# clock-temp-touch.net
KiCad netlist of a schematic drawn in Altium Designer
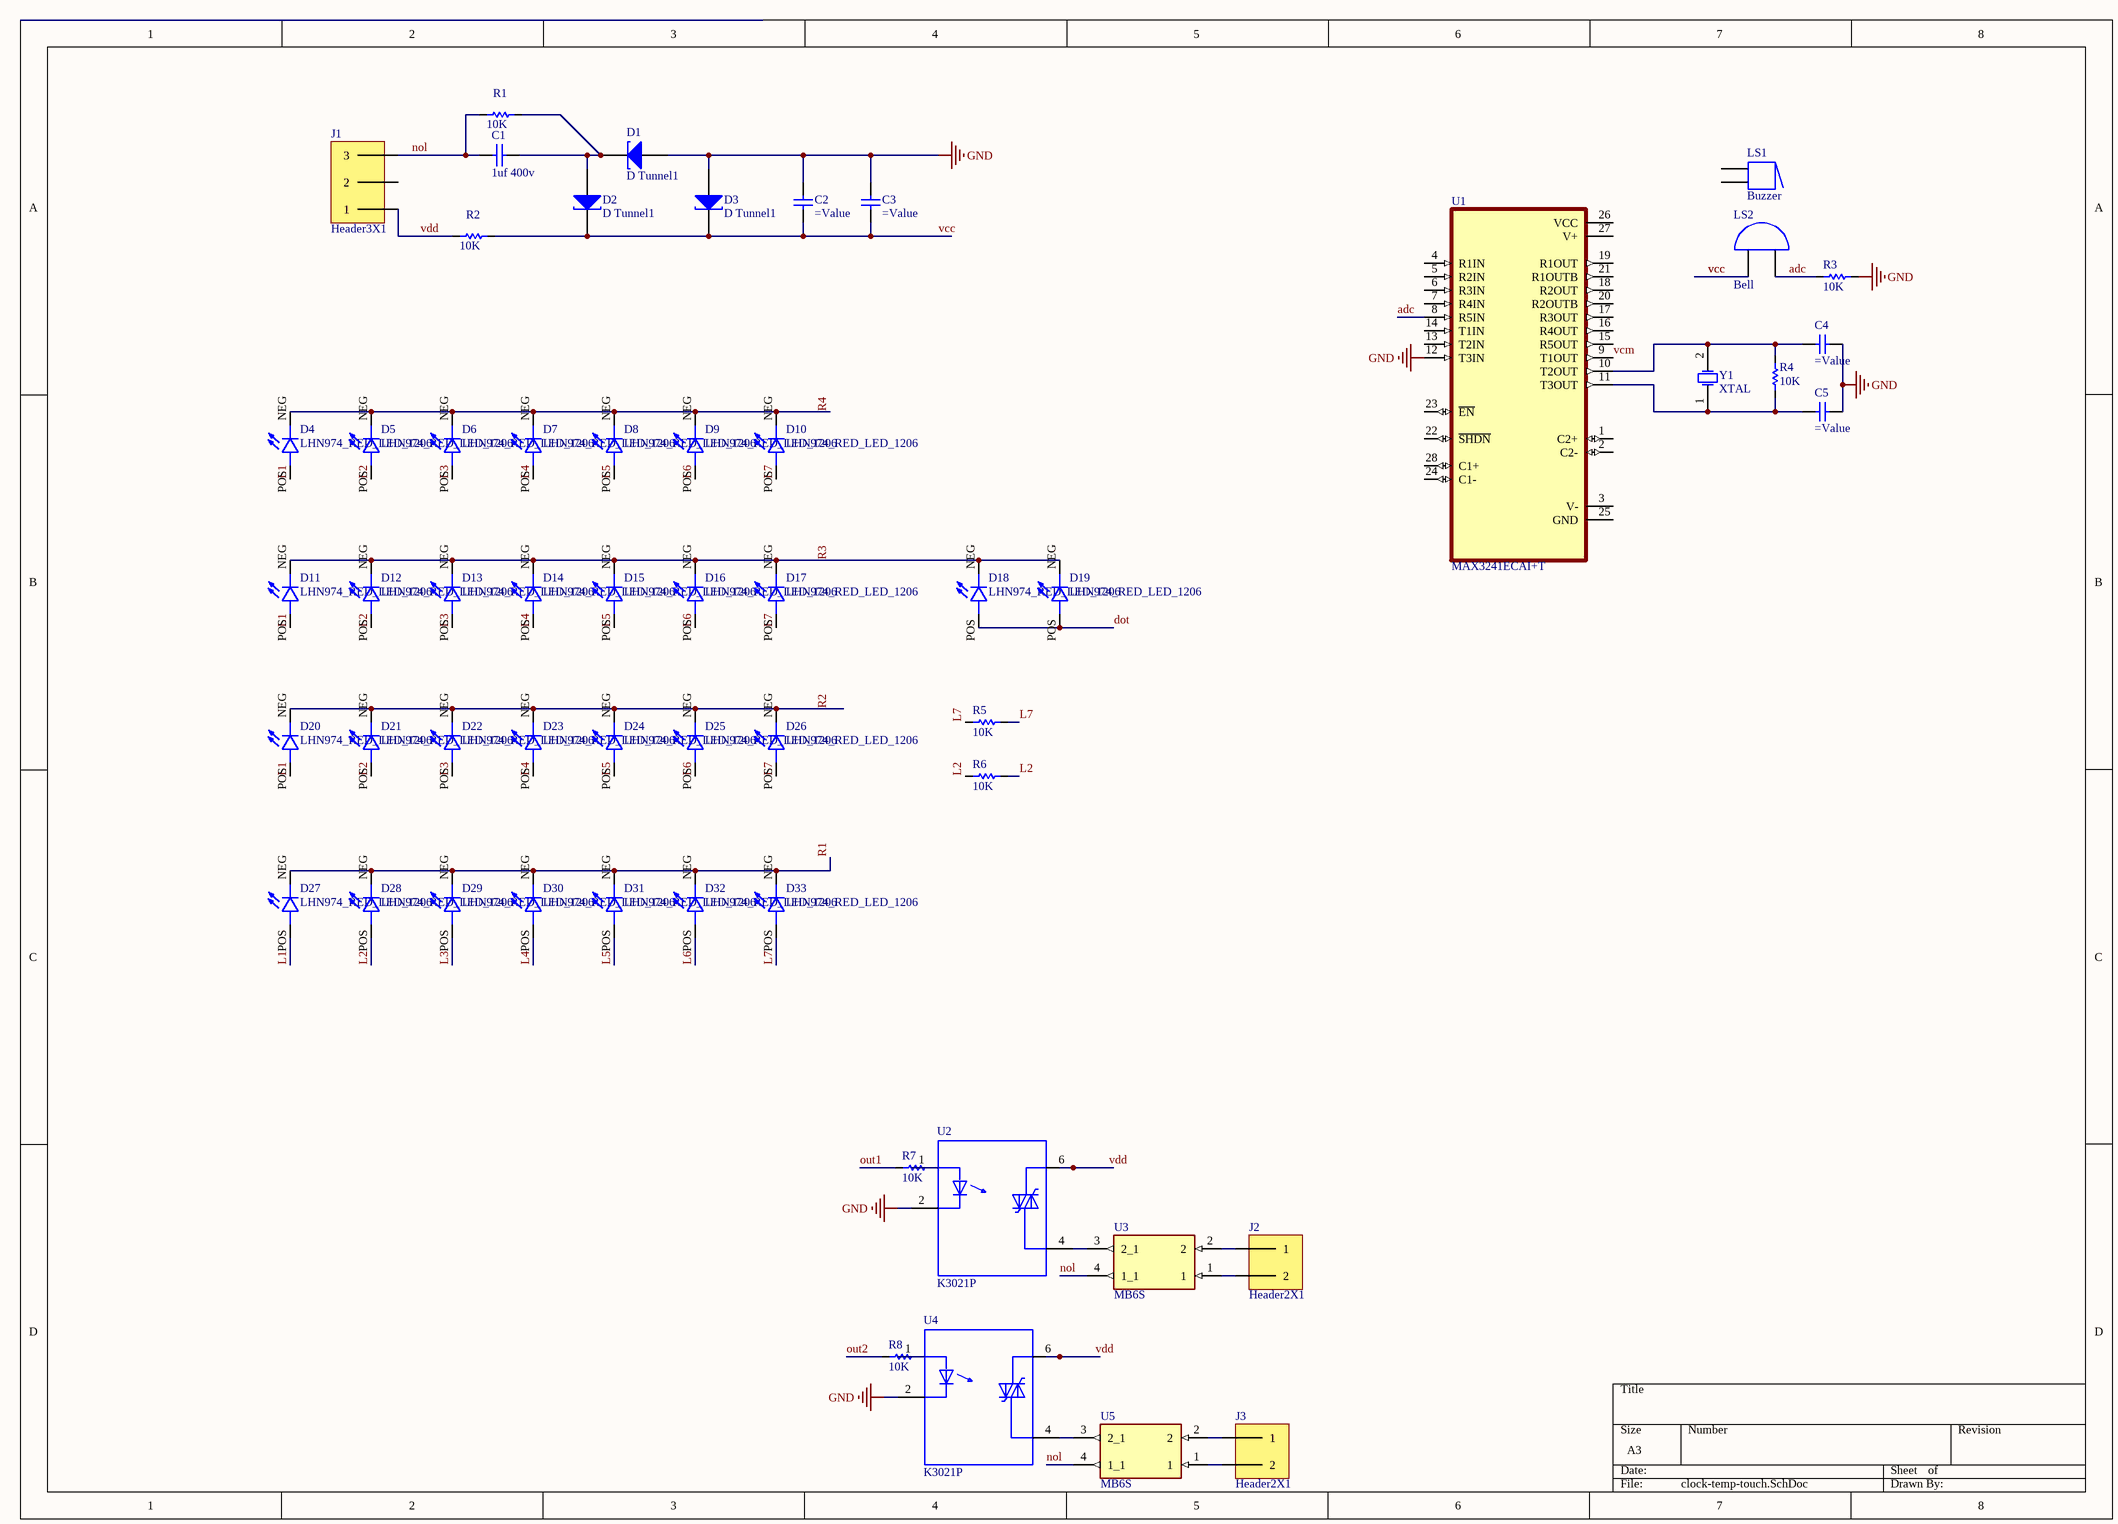
[diagram p0: clock-temp-touch.SchDoc]

(export (version "E")
  (design (tool "Eeschema 10.0.6"))
  (components
    (comp (ref "C1")
      (value "1uf 400v")
      (footprint "1uf 400v")
      (description "Capacitor 24*9mm")
      (fields (field (name "DESIGNER") "Seyed Mohsen Ghasemain"))
      (libsource (lib "PicPars.com_usefully_Library") (part "1uf 400v"))
    )
    (comp (ref "C2")
      (value "~")
      (footprint "CAP 1206")
      (description "Capacitor")
      (libsource (lib "AltiumLib1") (part "Capacitor"))
    )
    (comp (ref "C3")
      (value "~")
      (footprint "CAP 1206")
      (description "Capacitor")
      (libsource (lib "AltiumLib1") (part "Capacitor"))
    )
    (comp (ref "C4")
      (value "~")
      (footprint "CAP 1206")
      (description "Capacitor")
      (libsource (lib "AltiumLib1") (part "Capacitor"))
    )
    (comp (ref "C5")
      (value "~")
      (footprint "CAP 1206")
      (description "Capacitor")
      (libsource (lib "AltiumLib1") (part "Capacitor"))
    )
    (comp (ref "D1")
      (value "D Tunnel1")
      (footprint "3.2X1.6X1.1")
      (description "Tunnel Diode - RLC Model")
      (fields (field (name "PUBLISHER") "Altium Limited"))
      (libsource (lib "Miscellaneous Devices") (part "D Tunnel1"))
    )
    (comp (ref "D2")
      (value "D Tunnel1")
      (footprint "3.2X1.6X1.1")
      (description "Tunnel Diode - RLC Model")
      (fields (field (name "PUBLISHER") "Altium Limited"))
      (libsource (lib "Miscellaneous Devices") (part "D Tunnel1"))
    )
    (comp (ref "D3")
      (value "D Tunnel1")
      (footprint "3.2X1.6X1.1")
      (description "Tunnel Diode - RLC Model")
      (fields (field (name "PUBLISHER") "Altium Limited"))
      (libsource (lib "Miscellaneous Devices") (part "D Tunnel1"))
    )
    (comp (ref "D4")
      (value "LHN974_RED_LED_1206")
      (footprint "LEDC3216X120N")
      (description "2.6 V Red LED SMD")
      (fields (field (name "MP") "LHN974 RED LED 1206") (field (name "MF") "Osram"))
      (libsource (lib "LHN974_RED_LED_1206") (part "LHN974_RED_LED_1206"))
    )
    (comp (ref "D5")
      (value "LHN974_RED_LED_1206")
      (footprint "LEDC3216X120N")
      (description "2.6 V Red LED SMD")
      (fields (field (name "MP") "LHN974 RED LED 1206") (field (name "MF") "Osram"))
      (libsource (lib "LHN974_RED_LED_1206") (part "LHN974_RED_LED_1206"))
    )
    (comp (ref "D6")
      (value "LHN974_RED_LED_1206")
      (footprint "LEDC3216X120N")
      (description "2.6 V Red LED SMD")
      (fields (field (name "MP") "LHN974 RED LED 1206") (field (name "MF") "Osram"))
      (libsource (lib "LHN974_RED_LED_1206") (part "LHN974_RED_LED_1206"))
    )
    (comp (ref "D7")
      (value "LHN974_RED_LED_1206")
      (footprint "LEDC3216X120N")
      (description "2.6 V Red LED SMD")
      (fields (field (name "MP") "LHN974 RED LED 1206") (field (name "MF") "Osram"))
      (libsource (lib "LHN974_RED_LED_1206") (part "LHN974_RED_LED_1206"))
    )
    (comp (ref "D8")
      (value "LHN974_RED_LED_1206")
      (footprint "LEDC3216X120N")
      (description "2.6 V Red LED SMD")
      (fields (field (name "MP") "LHN974 RED LED 1206") (field (name "MF") "Osram"))
      (libsource (lib "LHN974_RED_LED_1206") (part "LHN974_RED_LED_1206"))
    )
    (comp (ref "D9")
      (value "LHN974_RED_LED_1206")
      (footprint "LEDC3216X120N")
      (description "2.6 V Red LED SMD")
      (fields (field (name "MP") "LHN974 RED LED 1206") (field (name "MF") "Osram"))
      (libsource (lib "LHN974_RED_LED_1206") (part "LHN974_RED_LED_1206"))
    )
    (comp (ref "D10")
      (value "LHN974_RED_LED_1206")
      (footprint "LEDC3216X120N")
      (description "2.6 V Red LED SMD")
      (fields (field (name "MP") "LHN974 RED LED 1206") (field (name "MF") "Osram"))
      (libsource (lib "LHN974_RED_LED_1206") (part "LHN974_RED_LED_1206"))
    )
    (comp (ref "D11")
      (value "LHN974_RED_LED_1206")
      (footprint "LEDC3216X120N")
      (description "2.6 V Red LED SMD")
      (fields (field (name "MP") "LHN974 RED LED 1206") (field (name "MF") "Osram"))
      (libsource (lib "LHN974_RED_LED_1206") (part "LHN974_RED_LED_1206"))
    )
    (comp (ref "D12")
      (value "LHN974_RED_LED_1206")
      (footprint "LEDC3216X120N")
      (description "2.6 V Red LED SMD")
      (fields (field (name "MP") "LHN974 RED LED 1206") (field (name "MF") "Osram"))
      (libsource (lib "LHN974_RED_LED_1206") (part "LHN974_RED_LED_1206"))
    )
    (comp (ref "D13")
      (value "LHN974_RED_LED_1206")
      (footprint "LEDC3216X120N")
      (description "2.6 V Red LED SMD")
      (fields (field (name "MP") "LHN974 RED LED 1206") (field (name "MF") "Osram"))
      (libsource (lib "LHN974_RED_LED_1206") (part "LHN974_RED_LED_1206"))
    )
    (comp (ref "D14")
      (value "LHN974_RED_LED_1206")
      (footprint "LEDC3216X120N")
      (description "2.6 V Red LED SMD")
      (fields (field (name "MP") "LHN974 RED LED 1206") (field (name "MF") "Osram"))
      (libsource (lib "LHN974_RED_LED_1206") (part "LHN974_RED_LED_1206"))
    )
    (comp (ref "D15")
      (value "LHN974_RED_LED_1206")
      (footprint "LEDC3216X120N")
      (description "2.6 V Red LED SMD")
      (fields (field (name "MP") "LHN974 RED LED 1206") (field (name "MF") "Osram"))
      (libsource (lib "LHN974_RED_LED_1206") (part "LHN974_RED_LED_1206"))
    )
    (comp (ref "D16")
      (value "LHN974_RED_LED_1206")
      (footprint "LEDC3216X120N")
      (description "2.6 V Red LED SMD")
      (fields (field (name "MP") "LHN974 RED LED 1206") (field (name "MF") "Osram"))
      (libsource (lib "LHN974_RED_LED_1206") (part "LHN974_RED_LED_1206"))
    )
    (comp (ref "D17")
      (value "LHN974_RED_LED_1206")
      (footprint "LEDC3216X120N")
      (description "2.6 V Red LED SMD")
      (fields (field (name "MP") "LHN974 RED LED 1206") (field (name "MF") "Osram"))
      (libsource (lib "LHN974_RED_LED_1206") (part "LHN974_RED_LED_1206"))
    )
    (comp (ref "D18")
      (value "LHN974_RED_LED_1206")
      (footprint "LEDC3216X120N")
      (description "2.6 V Red LED SMD")
      (fields (field (name "MP") "LHN974 RED LED 1206") (field (name "MF") "Osram"))
      (libsource (lib "LHN974_RED_LED_1206") (part "LHN974_RED_LED_1206"))
    )
    (comp (ref "D19")
      (value "LHN974_RED_LED_1206")
      (footprint "LEDC3216X120N")
      (description "2.6 V Red LED SMD")
      (fields (field (name "MP") "LHN974 RED LED 1206") (field (name "MF") "Osram"))
      (libsource (lib "LHN974_RED_LED_1206") (part "LHN974_RED_LED_1206"))
    )
    (comp (ref "D20")
      (value "LHN974_RED_LED_1206")
      (footprint "LEDC3216X120N")
      (description "2.6 V Red LED SMD")
      (fields (field (name "MP") "LHN974 RED LED 1206") (field (name "MF") "Osram"))
      (libsource (lib "LHN974_RED_LED_1206") (part "LHN974_RED_LED_1206"))
    )
    (comp (ref "D21")
      (value "LHN974_RED_LED_1206")
      (footprint "LEDC3216X120N")
      (description "2.6 V Red LED SMD")
      (fields (field (name "MP") "LHN974 RED LED 1206") (field (name "MF") "Osram"))
      (libsource (lib "LHN974_RED_LED_1206") (part "LHN974_RED_LED_1206"))
    )
    (comp (ref "D22")
      (value "LHN974_RED_LED_1206")
      (footprint "LEDC3216X120N")
      (description "2.6 V Red LED SMD")
      (fields (field (name "MP") "LHN974 RED LED 1206") (field (name "MF") "Osram"))
      (libsource (lib "LHN974_RED_LED_1206") (part "LHN974_RED_LED_1206"))
    )
    (comp (ref "D23")
      (value "LHN974_RED_LED_1206")
      (footprint "LEDC3216X120N")
      (description "2.6 V Red LED SMD")
      (fields (field (name "MP") "LHN974 RED LED 1206") (field (name "MF") "Osram"))
      (libsource (lib "LHN974_RED_LED_1206") (part "LHN974_RED_LED_1206"))
    )
    (comp (ref "D24")
      (value "LHN974_RED_LED_1206")
      (footprint "LEDC3216X120N")
      (description "2.6 V Red LED SMD")
      (fields (field (name "MP") "LHN974 RED LED 1206") (field (name "MF") "Osram"))
      (libsource (lib "LHN974_RED_LED_1206") (part "LHN974_RED_LED_1206"))
    )
    (comp (ref "D25")
      (value "LHN974_RED_LED_1206")
      (footprint "LEDC3216X120N")
      (description "2.6 V Red LED SMD")
      (fields (field (name "MP") "LHN974 RED LED 1206") (field (name "MF") "Osram"))
      (libsource (lib "LHN974_RED_LED_1206") (part "LHN974_RED_LED_1206"))
    )
    (comp (ref "D26")
      (value "LHN974_RED_LED_1206")
      (footprint "LEDC3216X120N")
      (description "2.6 V Red LED SMD")
      (fields (field (name "MP") "LHN974 RED LED 1206") (field (name "MF") "Osram"))
      (libsource (lib "LHN974_RED_LED_1206") (part "LHN974_RED_LED_1206"))
    )
    (comp (ref "D27")
      (value "LHN974_RED_LED_1206")
      (footprint "LEDC3216X120N")
      (description "2.6 V Red LED SMD")
      (fields (field (name "MP") "LHN974 RED LED 1206") (field (name "MF") "Osram"))
      (libsource (lib "LHN974_RED_LED_1206") (part "LHN974_RED_LED_1206"))
    )
    (comp (ref "D28")
      (value "LHN974_RED_LED_1206")
      (footprint "LEDC3216X120N")
      (description "2.6 V Red LED SMD")
      (fields (field (name "MP") "LHN974 RED LED 1206") (field (name "MF") "Osram"))
      (libsource (lib "LHN974_RED_LED_1206") (part "LHN974_RED_LED_1206"))
    )
    (comp (ref "D29")
      (value "LHN974_RED_LED_1206")
      (footprint "LEDC3216X120N")
      (description "2.6 V Red LED SMD")
      (fields (field (name "MP") "LHN974 RED LED 1206") (field (name "MF") "Osram"))
      (libsource (lib "LHN974_RED_LED_1206") (part "LHN974_RED_LED_1206"))
    )
    (comp (ref "D30")
      (value "LHN974_RED_LED_1206")
      (footprint "LEDC3216X120N")
      (description "2.6 V Red LED SMD")
      (fields (field (name "MP") "LHN974 RED LED 1206") (field (name "MF") "Osram"))
      (libsource (lib "LHN974_RED_LED_1206") (part "LHN974_RED_LED_1206"))
    )
    (comp (ref "D31")
      (value "LHN974_RED_LED_1206")
      (footprint "LEDC3216X120N")
      (description "2.6 V Red LED SMD")
      (fields (field (name "MP") "LHN974 RED LED 1206") (field (name "MF") "Osram"))
      (libsource (lib "LHN974_RED_LED_1206") (part "LHN974_RED_LED_1206"))
    )
    (comp (ref "D32")
      (value "LHN974_RED_LED_1206")
      (footprint "LEDC3216X120N")
      (description "2.6 V Red LED SMD")
      (fields (field (name "MP") "LHN974 RED LED 1206") (field (name "MF") "Osram"))
      (libsource (lib "LHN974_RED_LED_1206") (part "LHN974_RED_LED_1206"))
    )
    (comp (ref "D33")
      (value "LHN974_RED_LED_1206")
      (footprint "LEDC3216X120N")
      (description "2.6 V Red LED SMD")
      (fields (field (name "MP") "LHN974 RED LED 1206") (field (name "MF") "Osram"))
      (libsource (lib "LHN974_RED_LED_1206") (part "LHN974_RED_LED_1206"))
    )
    (comp (ref "J1")
      (value "Header3X1")
      (footprint "HEADER 3X1")
      (libsource (lib "AltiumLib1") (part "Header3X1"))
    )
    (comp (ref "J2")
      (value "Header2X1")
      (footprint "Header 2X1")
      (libsource (lib "AltiumLib1") (part "Header2X1"))
    )
    (comp (ref "J3")
      (value "Header2X1")
      (footprint "Header 2X1")
      (libsource (lib "AltiumLib1") (part "Header2X1"))
    )
    (comp (ref "LS1")
      (value "Buzzer")
      (footprint "ABSM-1574")
      (description "Magnetic Transducer Buzzer")
      (fields (field (name "PUBLISHER") "Altium Limited"))
      (libsource (lib "Miscellaneous Devices") (part "Buzzer"))
    )
    (comp (ref "LS2")
      (value "Bell")
      (footprint "PIN2")
      (description "Electrical Bell")
      (fields (field (name "PUBLISHER") "Altium Limited"))
      (libsource (lib "Miscellaneous Devices") (part "Bell"))
    )
    (comp (ref "R1")
      (value "10K")
      (footprint "RES 1206 (3216X08L)")
      (description "Resistor")
      (fields (field (name "TOLERANCE") "5%") (field (name "POWER") "1/4 W"))
      (libsource (lib "AltiumLib1") (part "Resistor"))
    )
    (comp (ref "R2")
      (value "10K")
      (footprint "Res-(2/1)")
      (description "Resistor")
      (fields (field (name "TOLERANCE") "5%") (field (name "POWER") "1/4 W"))
      (libsource (lib "AltiumLib1") (part "Resistor"))
    )
    (comp (ref "R3")
      (value "10K")
      (footprint "RES 1206 (3216X08L)")
      (description "Resistor")
      (fields (field (name "TOLERANCE") "5%") (field (name "POWER") "1/4 W"))
      (libsource (lib "AltiumLib1") (part "Resistor"))
    )
    (comp (ref "R4")
      (value "10K")
      (footprint "RES 1206 (3216X08L)")
      (description "Resistor")
      (fields (field (name "TOLERANCE") "5%") (field (name "POWER") "1/4 W"))
      (libsource (lib "AltiumLib1") (part "Resistor"))
    )
    (comp (ref "R5")
      (value "10K")
      (footprint "RES 1206 (3216X08L)")
      (description "Resistor")
      (fields (field (name "TOLERANCE") "5%") (field (name "POWER") "1/4 W"))
      (libsource (lib "AltiumLib1") (part "Resistor"))
    )
    (comp (ref "R6")
      (value "10K")
      (footprint "RES 1206 (3216X08L)")
      (description "Resistor")
      (fields (field (name "TOLERANCE") "5%") (field (name "POWER") "1/4 W"))
      (libsource (lib "AltiumLib1") (part "Resistor"))
    )
    (comp (ref "R7")
      (value "10K")
      (footprint "RES 1206 (3216X08L)")
      (description "Resistor")
      (fields (field (name "TOLERANCE") "5%") (field (name "POWER") "1/4 W"))
      (libsource (lib "AltiumLib1") (part "Resistor"))
    )
    (comp (ref "R8")
      (value "10K")
      (footprint "RES 1206 (3216X08L)")
      (description "Resistor")
      (fields (field (name "TOLERANCE") "5%") (field (name "POWER") "1/4 W"))
      (libsource (lib "AltiumLib1") (part "Resistor"))
    )
    (comp (ref "U1")
      (value "MAX3241ECAI+T")
      (footprint "SOP65P777X199-28N")
      (description "±15kV ESD-Protected, Down to 10nA, 3.0V to 5.5V, Up to 1Mbps, True RS-232 Transceivers")
      (fields (field (name "MF") "Analog Devices"))
      (libsource (lib "ssop28") (part "MAX3241ECAI+T"))
    )
    (comp (ref "U2")
      (value "K3021P")
      (footprint "DIP762W50P254L730H410Q6")
      (description "Optoisolator Triac Output 5300Vrms 1 Channel 6-DIP")
      (fields (field (name "MF") "Vishay Semiconductor"))
      (libsource (lib "K3021P") (part "K3021P"))
    )
    (comp (ref "U3")
      (value "MB6S")
      (footprint "SOIC245P670X270-4N")
      (description "Bridge Rectifier Single Phase Standard 600V Surface Mount 4-SOIC")
      (fields (field (name "MF") "ON Semiconductor") (field (name "DIGI-KEY_PART_NUMBER") "MB6SCT-ND"))
      (libsource (lib "MB6S") (part "MB6S"))
    )
    (comp (ref "U4")
      (value "K3021P")
      (footprint "DIP762W50P254L730H410Q6")
      (description "Optoisolator Triac Output 5300Vrms 1 Channel 6-DIP")
      (fields (field (name "MF") "Vishay Semiconductor"))
      (libsource (lib "K3021P") (part "K3021P"))
    )
    (comp (ref "U5")
      (value "MB6S")
      (footprint "SOIC245P670X270-4N")
      (description "Bridge Rectifier Single Phase Standard 600V Surface Mount 4-SOIC")
      (fields (field (name "MF") "ON Semiconductor") (field (name "DIGI-KEY_PART_NUMBER") "MB6SCT-ND"))
      (libsource (lib "MB6S") (part "MB6S"))
    )
    (comp (ref "Y1")
      (value "XTAL")
      (footprint "R38")
      (description "Crystal Oscillator")
      (fields (field (name "PUBLISHER") "Altium Limited"))
      (libsource (lib "Miscellaneous Devices") (part "XTAL"))
    )
  )
  (nets
    (net (code "1") (name "/L1") (class "Default")
      (node (ref "D11") (pin "POS") (pinfunction "POS_POS") (pintype "passive"))
      (node (ref "D20") (pin "POS") (pinfunction "POS_POS") (pintype "passive"))
      (node (ref "D27") (pin "POS") (pinfunction "POS_POS") (pintype "passive"))
      (node (ref "D4") (pin "POS") (pinfunction "POS_POS") (pintype "passive"))
    )
    (net (code "2") (name "/L2") (class "Default")
      (node (ref "D12") (pin "POS") (pinfunction "POS_POS") (pintype "passive"))
      (node (ref "D21") (pin "POS") (pinfunction "POS_POS") (pintype "passive"))
      (node (ref "D28") (pin "POS") (pinfunction "POS_POS") (pintype "passive"))
      (node (ref "D5") (pin "POS") (pinfunction "POS_POS") (pintype "passive"))
      (node (ref "R6") (pin "1") (pinfunction "1_1") (pintype "passive"))
      (node (ref "R6") (pin "2") (pinfunction "2_2") (pintype "passive"))
    )
    (net (code "3") (name "/L3") (class "Default")
      (node (ref "D13") (pin "POS") (pinfunction "POS_POS") (pintype "passive"))
      (node (ref "D22") (pin "POS") (pinfunction "POS_POS") (pintype "passive"))
      (node (ref "D29") (pin "POS") (pinfunction "POS_POS") (pintype "passive"))
      (node (ref "D6") (pin "POS") (pinfunction "POS_POS") (pintype "passive"))
    )
    (net (code "4") (name "/L4") (class "Default")
      (node (ref "D14") (pin "POS") (pinfunction "POS_POS") (pintype "passive"))
      (node (ref "D23") (pin "POS") (pinfunction "POS_POS") (pintype "passive"))
      (node (ref "D30") (pin "POS") (pinfunction "POS_POS") (pintype "passive"))
      (node (ref "D7") (pin "POS") (pinfunction "POS_POS") (pintype "passive"))
    )
    (net (code "5") (name "/L5") (class "Default")
      (node (ref "D15") (pin "POS") (pinfunction "POS_POS") (pintype "passive"))
      (node (ref "D24") (pin "POS") (pinfunction "POS_POS") (pintype "passive"))
      (node (ref "D31") (pin "POS") (pinfunction "POS_POS") (pintype "passive"))
      (node (ref "D8") (pin "POS") (pinfunction "POS_POS") (pintype "passive"))
    )
    (net (code "6") (name "/L6") (class "Default")
      (node (ref "D16") (pin "POS") (pinfunction "POS_POS") (pintype "passive"))
      (node (ref "D25") (pin "POS") (pinfunction "POS_POS") (pintype "passive"))
      (node (ref "D32") (pin "POS") (pinfunction "POS_POS") (pintype "passive"))
      (node (ref "D9") (pin "POS") (pinfunction "POS_POS") (pintype "passive"))
    )
    (net (code "7") (name "/L7") (class "Default")
      (node (ref "D10") (pin "POS") (pinfunction "POS_POS") (pintype "passive"))
      (node (ref "D17") (pin "POS") (pinfunction "POS_POS") (pintype "passive"))
      (node (ref "D26") (pin "POS") (pinfunction "POS_POS") (pintype "passive"))
      (node (ref "D33") (pin "POS") (pinfunction "POS_POS") (pintype "passive"))
      (node (ref "R5") (pin "1") (pinfunction "1_1") (pintype "passive"))
      (node (ref "R5") (pin "2") (pinfunction "2_2") (pintype "passive"))
    )
    (net (code "8") (name "/R1") (class "Default")
      (node (ref "D27") (pin "NEG") (pinfunction "NEG_NEG") (pintype "passive"))
      (node (ref "D28") (pin "NEG") (pinfunction "NEG_NEG") (pintype "passive"))
      (node (ref "D29") (pin "NEG") (pinfunction "NEG_NEG") (pintype "passive"))
      (node (ref "D30") (pin "NEG") (pinfunction "NEG_NEG") (pintype "passive"))
      (node (ref "D31") (pin "NEG") (pinfunction "NEG_NEG") (pintype "passive"))
      (node (ref "D32") (pin "NEG") (pinfunction "NEG_NEG") (pintype "passive"))
      (node (ref "D33") (pin "NEG") (pinfunction "NEG_NEG") (pintype "passive"))
    )
    (net (code "9") (name "/R2") (class "Default")
      (node (ref "D20") (pin "NEG") (pinfunction "NEG_NEG") (pintype "passive"))
      (node (ref "D21") (pin "NEG") (pinfunction "NEG_NEG") (pintype "passive"))
      (node (ref "D22") (pin "NEG") (pinfunction "NEG_NEG") (pintype "passive"))
      (node (ref "D23") (pin "NEG") (pinfunction "NEG_NEG") (pintype "passive"))
      (node (ref "D24") (pin "NEG") (pinfunction "NEG_NEG") (pintype "passive"))
      (node (ref "D25") (pin "NEG") (pinfunction "NEG_NEG") (pintype "passive"))
      (node (ref "D26") (pin "NEG") (pinfunction "NEG_NEG") (pintype "passive"))
    )
    (net (code "10") (name "/R3") (class "Default")
      (node (ref "D11") (pin "NEG") (pinfunction "NEG_NEG") (pintype "passive"))
      (node (ref "D12") (pin "NEG") (pinfunction "NEG_NEG") (pintype "passive"))
      (node (ref "D13") (pin "NEG") (pinfunction "NEG_NEG") (pintype "passive"))
      (node (ref "D14") (pin "NEG") (pinfunction "NEG_NEG") (pintype "passive"))
      (node (ref "D15") (pin "NEG") (pinfunction "NEG_NEG") (pintype "passive"))
      (node (ref "D16") (pin "NEG") (pinfunction "NEG_NEG") (pintype "passive"))
      (node (ref "D17") (pin "NEG") (pinfunction "NEG_NEG") (pintype "passive"))
      (node (ref "D18") (pin "NEG") (pinfunction "NEG_NEG") (pintype "passive"))
      (node (ref "D19") (pin "NEG") (pinfunction "NEG_NEG") (pintype "passive"))
    )
    (net (code "11") (name "/R4") (class "Default")
      (node (ref "D10") (pin "NEG") (pinfunction "NEG_NEG") (pintype "passive"))
      (node (ref "D4") (pin "NEG") (pinfunction "NEG_NEG") (pintype "passive"))
      (node (ref "D5") (pin "NEG") (pinfunction "NEG_NEG") (pintype "passive"))
      (node (ref "D6") (pin "NEG") (pinfunction "NEG_NEG") (pintype "passive"))
      (node (ref "D7") (pin "NEG") (pinfunction "NEG_NEG") (pintype "passive"))
      (node (ref "D8") (pin "NEG") (pinfunction "NEG_NEG") (pintype "passive"))
      (node (ref "D9") (pin "NEG") (pinfunction "NEG_NEG") (pintype "passive"))
    )
    (net (code "12") (name "/adc") (class "Default")
      (node (ref "LS2") (pin "2") (pinfunction "B_2") (pintype "passive"))
      (node (ref "R3") (pin "2") (pinfunction "2_2") (pintype "passive"))
      (node (ref "U1") (pin "8") (pinfunction "R5IN_8") (pintype "input"))
    )
    (net (code "13") (name "/dot") (class "Default")
      (node (ref "D18") (pin "POS") (pinfunction "POS_POS") (pintype "passive"))
      (node (ref "D19") (pin "POS") (pinfunction "POS_POS") (pintype "passive"))
    )
    (net (code "14") (name "/nol") (class "Default")
      (node (ref "C1") (pin "1") (pinfunction "1_1") (pintype "passive"))
      (node (ref "J1") (pin "3") (pinfunction "3_3") (pintype "passive"))
      (node (ref "R1") (pin "1") (pinfunction "1_1") (pintype "passive"))
      (node (ref "U3") (pin "4") (pinfunction "1_1_4") (pintype "output"))
      (node (ref "U5") (pin "4") (pinfunction "1_1_4") (pintype "output"))
    )
    (net (code "15") (name "/out1") (class "Default")
      (node (ref "R7") (pin "2") (pinfunction "2_2") (pintype "passive"))
    )
    (net (code "16") (name "/out2") (class "Default")
      (node (ref "R8") (pin "2") (pinfunction "2_2") (pintype "passive"))
    )
    (net (code "17") (name "/vcc") (class "Default")
      (node (ref "C2") (pin "1") (pinfunction "+_1") (pintype "passive"))
      (node (ref "C3") (pin "1") (pinfunction "+_1") (pintype "passive"))
      (node (ref "D2") (pin "2") (pinfunction "K_2") (pintype "passive"))
      (node (ref "D3") (pin "2") (pinfunction "K_2") (pintype "passive"))
      (node (ref "LS2") (pin "1") (pinfunction "A_1") (pintype "passive"))
      (node (ref "R2") (pin "2") (pinfunction "2_2") (pintype "passive"))
    )
    (net (code "18") (name "/vcm") (class "Default")
      (node (ref "U1") (pin "9") (pinfunction "T1OUT_9") (pintype "output"))
    )
    (net (code "19") (name "/vdd") (class "Default")
      (node (ref "J1") (pin "1") (pinfunction "1_1") (pintype "passive"))
      (node (ref "R2") (pin "1") (pinfunction "1_1") (pintype "passive"))
      (node (ref "U2") (pin "6") (pinfunction "MT2_6") (pintype "passive"))
      (node (ref "U4") (pin "6") (pinfunction "MT2_6") (pintype "passive"))
    )
    (net (code "20") (name "GND") (class "Default")
      (node (ref "C2") (pin "2") (pinfunction "-_2") (pintype "passive"))
      (node (ref "C3") (pin "2") (pinfunction "-_2") (pintype "passive"))
      (node (ref "C4") (pin "1") (pinfunction "+_1") (pintype "passive"))
      (node (ref "C5") (pin "1") (pinfunction "+_1") (pintype "passive"))
      (node (ref "D1") (pin "1") (pinfunction "A_1") (pintype "passive"))
      (node (ref "D3") (pin "1") (pinfunction "A_1") (pintype "passive"))
      (node (ref "R3") (pin "1") (pinfunction "1_1") (pintype "passive"))
      (node (ref "U1") (pin "12") (pinfunction "T3IN_12") (pintype "input"))
      (node (ref "U2") (pin "2") (pinfunction "C_2") (pintype "passive"))
      (node (ref "U4") (pin "2") (pinfunction "C_2") (pintype "passive"))
    )
    (net (code "21") (name "Net-(C4--)") (class "Default")
      (node (ref "C4") (pin "2") (pinfunction "-_2") (pintype "passive"))
      (node (ref "R4") (pin "2") (pinfunction "2_2") (pintype "passive"))
      (node (ref "U1") (pin "10") (pinfunction "T2OUT_10") (pintype "output"))
      (node (ref "Y1") (pin "2") (pinfunction "OSC2_2") (pintype "passive"))
    )
    (net (code "22") (name "Net-(C5--)") (class "Default")
      (node (ref "C5") (pin "2") (pinfunction "-_2") (pintype "passive"))
      (node (ref "R4") (pin "1") (pinfunction "1_1") (pintype "passive"))
      (node (ref "U1") (pin "11") (pinfunction "T3OUT_11") (pintype "output"))
      (node (ref "Y1") (pin "1") (pinfunction "OSC1_1") (pintype "passive"))
    )
    (net (code "23") (name "Net-(D1-K)") (class "Default")
      (node (ref "C1") (pin "2") (pinfunction "2_2") (pintype "passive"))
      (node (ref "D1") (pin "2") (pinfunction "K_2") (pintype "passive"))
      (node (ref "D2") (pin "1") (pinfunction "A_1") (pintype "passive"))
      (node (ref "R1") (pin "2") (pinfunction "2_2") (pintype "passive"))
    )
    (net (code "24") (name "Net-(J2-Pad1)") (class "Default")
      (node (ref "J2") (pin "1") (pinfunction "1_1") (pintype "passive"))
      (node (ref "U3") (pin "2") (pinfunction "2_2") (pintype "input"))
    )
    (net (code "25") (name "Net-(J2-Pad2)") (class "Default")
      (node (ref "J2") (pin "2") (pinfunction "2_2") (pintype "passive"))
      (node (ref "U3") (pin "1") (pinfunction "1_1") (pintype "input"))
    )
    (net (code "26") (name "Net-(J3-Pad1)") (class "Default")
      (node (ref "J3") (pin "1") (pinfunction "1_1") (pintype "passive"))
      (node (ref "U5") (pin "2") (pinfunction "2_2") (pintype "input"))
    )
    (net (code "27") (name "Net-(J3-Pad2)") (class "Default")
      (node (ref "J3") (pin "2") (pinfunction "2_2") (pintype "passive"))
      (node (ref "U5") (pin "1") (pinfunction "1_1") (pintype "input"))
    )
    (net (code "28") (name "Net-(LS1-Pad1)") (class "Default")
      (node (ref "LS1") (pin "1") (pinfunction "1_1") (pintype "passive"))
      (node (ref "LS1") (pin "1A") (pinfunction "1A_1A") (pintype "passive"))
    )
    (net (code "29") (name "Net-(LS1-Pad2)") (class "Default")
      (node (ref "LS1") (pin "2") (pinfunction "2_2") (pintype "passive"))
      (node (ref "LS1") (pin "2A") (pinfunction "2A_2A") (pintype "passive"))
    )
    (net (code "30") (name "Net-(U2-A)") (class "Default")
      (node (ref "R7") (pin "1") (pinfunction "1_1") (pintype "passive"))
      (node (ref "U2") (pin "1") (pinfunction "A_1") (pintype "passive"))
    )
    (net (code "31") (name "Net-(U2-MT1)") (class "Default")
      (node (ref "U2") (pin "4") (pinfunction "MT1_4") (pintype "passive"))
      (node (ref "U3") (pin "3") (pinfunction "2_1_3") (pintype "output"))
    )
    (net (code "32") (name "Net-(U4-A)") (class "Default")
      (node (ref "R8") (pin "1") (pinfunction "1_1") (pintype "passive"))
      (node (ref "U4") (pin "1") (pinfunction "A_1") (pintype "passive"))
    )
    (net (code "33") (name "Net-(U4-MT1)") (class "Default")
      (node (ref "U4") (pin "4") (pinfunction "MT1_4") (pintype "passive"))
      (node (ref "U5") (pin "3") (pinfunction "2_1_3") (pintype "output"))
    )
    (net (code "34") (name "unconnected-(J1-Pad2)") (class "Default")
      (node (ref "J1") (pin "2") (pinfunction "2_2") (pintype "passive"))
    )
    (net (code "35") (name "unconnected-(U1-C1+-Pad28)") (class "Default")
      (node (ref "U1") (pin "28") (pinfunction "C1+_28") (pintype "bidirectional"))
    )
    (net (code "36") (name "unconnected-(U1-C1--Pad24)") (class "Default")
      (node (ref "U1") (pin "24") (pinfunction "C1-_24") (pintype "bidirectional"))
    )
    (net (code "37") (name "unconnected-(U1-C2+-Pad1)") (class "Default")
      (node (ref "U1") (pin "1") (pinfunction "C2+_1") (pintype "bidirectional"))
    )
    (net (code "38") (name "unconnected-(U1-C2--Pad2)") (class "Default")
      (node (ref "U1") (pin "2") (pinfunction "C2-_2") (pintype "bidirectional"))
    )
    (net (code "39") (name "unconnected-(U1-GND-Pad25)") (class "Default")
      (node (ref "U1") (pin "25") (pinfunction "GND_25") (pintype "power_in"))
    )
    (net (code "40") (name "unconnected-(U1-R1IN-Pad4)") (class "Default")
      (node (ref "U1") (pin "4") (pinfunction "R1IN_4") (pintype "input"))
    )
    (net (code "41") (name "unconnected-(U1-R1OUT-Pad19)") (class "Default")
      (node (ref "U1") (pin "19") (pinfunction "R1OUT_19") (pintype "output"))
    )
    (net (code "42") (name "unconnected-(U1-R1OUTB-Pad21)") (class "Default")
      (node (ref "U1") (pin "21") (pinfunction "R1OUTB_21") (pintype "output"))
    )
    (net (code "43") (name "unconnected-(U1-R2IN-Pad5)") (class "Default")
      (node (ref "U1") (pin "5") (pinfunction "R2IN_5") (pintype "input"))
    )
    (net (code "44") (name "unconnected-(U1-R2OUT-Pad18)") (class "Default")
      (node (ref "U1") (pin "18") (pinfunction "R2OUT_18") (pintype "output"))
    )
    (net (code "45") (name "unconnected-(U1-R2OUTB-Pad20)") (class "Default")
      (node (ref "U1") (pin "20") (pinfunction "R2OUTB_20") (pintype "output"))
    )
    (net (code "46") (name "unconnected-(U1-R3IN-Pad6)") (class "Default")
      (node (ref "U1") (pin "6") (pinfunction "R3IN_6") (pintype "input"))
    )
    (net (code "47") (name "unconnected-(U1-R3OUT-Pad17)") (class "Default")
      (node (ref "U1") (pin "17") (pinfunction "R3OUT_17") (pintype "output"))
    )
    (net (code "48") (name "unconnected-(U1-R4IN-Pad7)") (class "Default")
      (node (ref "U1") (pin "7") (pinfunction "R4IN_7") (pintype "input"))
    )
    (net (code "49") (name "unconnected-(U1-R4OUT-Pad16)") (class "Default")
      (node (ref "U1") (pin "16") (pinfunction "R4OUT_16") (pintype "output"))
    )
    (net (code "50") (name "unconnected-(U1-R5OUT-Pad15)") (class "Default")
      (node (ref "U1") (pin "15") (pinfunction "R5OUT_15") (pintype "output"))
    )
    (net (code "51") (name "unconnected-(U1-T1IN-Pad14)") (class "Default")
      (node (ref "U1") (pin "14") (pinfunction "T1IN_14") (pintype "input"))
    )
    (net (code "52") (name "unconnected-(U1-T2IN-Pad13)") (class "Default")
      (node (ref "U1") (pin "13") (pinfunction "T2IN_13") (pintype "input"))
    )
    (net (code "53") (name "unconnected-(U1-V+-Pad27)") (class "Default")
      (node (ref "U1") (pin "27") (pinfunction "V+_27") (pintype "power_in"))
    )
    (net (code "54") (name "unconnected-(U1-V--Pad3)") (class "Default")
      (node (ref "U1") (pin "3") (pinfunction "V-_3") (pintype "power_in"))
    )
    (net (code "55") (name "unconnected-(U1-VCC-Pad26)") (class "Default")
      (node (ref "U1") (pin "26") (pinfunction "VCC_26") (pintype "power_in"))
    )
    (net (code "56") (name "unconnected-(U1-~{EN}-Pad23)") (class "Default")
      (node (ref "U1") (pin "23") (pinfunction "~{EN}_23") (pintype "bidirectional"))
    )
    (net (code "57") (name "unconnected-(U1-~{SHDN}-Pad22)") (class "Default")
      (node (ref "U1") (pin "22") (pinfunction "~{SHDN}_22") (pintype "bidirectional"))
    )
  )
)
